# Sens_BMP085_HIH613x.net
KiCad netlist of a schematic drawn in EAGLE
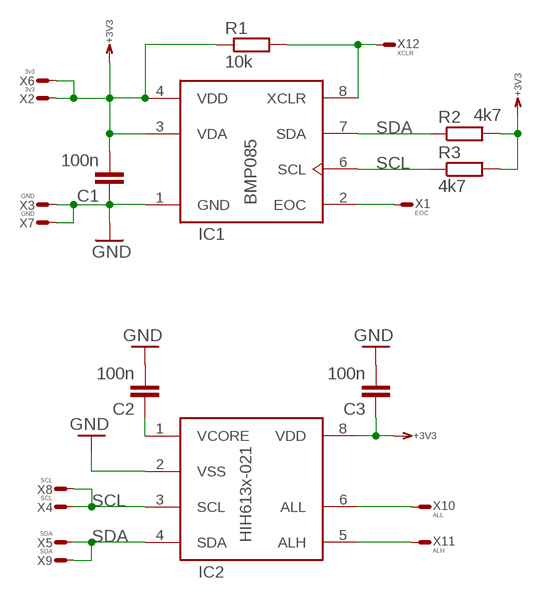
[diagram p0: schematic, sheet 1]

(export (version "E")
  (design (tool "Eeschema 10.0.6"))
  (components
    (comp (ref "C1")
      (value "100n")
      (footprint "eagle-import:0603")
      (libsource (lib "eagle-import") (part "C0603"))
    )
    (comp (ref "C2")
      (value "100n")
      (footprint "eagle-import:0603")
      (libsource (lib "eagle-import") (part "C0603"))
    )
    (comp (ref "C3")
      (value "100n")
      (footprint "eagle-import:0603")
      (libsource (lib "eagle-import") (part "C0603"))
    )
    (comp (ref "IC1")
      (value "BMP085")
      (footprint "eagle-import:LCC8")
      (libsource (lib "eagle-import") (part "BMP085"))
    )
    (comp (ref "IC2")
      (value "HIH613x-021")
      (footprint "eagle-import:SO8")
      (libsource (lib "eagle-import") (part "HIH613X"))
    )
    (comp (ref "R1")
      (value "10k")
      (footprint "eagle-import:0603")
      (libsource (lib "eagle-import") (part "R0603"))
    )
    (comp (ref "R2")
      (value "4k7")
      (footprint "eagle-import:0603")
      (libsource (lib "eagle-import") (part "R0603"))
    )
    (comp (ref "R3")
      (value "4k7")
      (footprint "eagle-import:0603")
      (libsource (lib "eagle-import") (part "R0603"))
    )
    (comp (ref "X1")
      (value "EOC")
      (footprint "eagle-import:S1.27R")
      (libsource (lib "eagle-import") (part "WIREPADR"))
    )
    (comp (ref "X2")
      (value "3v3")
      (footprint "eagle-import:T1.6_0.9")
      (libsource (lib "eagle-import") (part "WIREPADT1.6/0.9"))
    )
    (comp (ref "X3")
      (value "GND")
      (footprint "eagle-import:T1.6_0.9")
      (libsource (lib "eagle-import") (part "WIREPADT1.6/0.9"))
    )
    (comp (ref "X4")
      (value "SCL")
      (footprint "eagle-import:T1.6_0.9")
      (libsource (lib "eagle-import") (part "WIREPADT1.6/0.9"))
    )
    (comp (ref "X5")
      (value "SDA")
      (footprint "eagle-import:T1.6_0.9")
      (libsource (lib "eagle-import") (part "WIREPADT1.6/0.9"))
    )
    (comp (ref "X6")
      (value "3v3")
      (footprint "eagle-import:T1.6_0.9")
      (libsource (lib "eagle-import") (part "WIREPADT1.6/0.9"))
    )
    (comp (ref "X7")
      (value "GND")
      (footprint "eagle-import:T1.6_0.9")
      (libsource (lib "eagle-import") (part "WIREPADT1.6/0.9"))
    )
    (comp (ref "X8")
      (value "SCL")
      (footprint "eagle-import:T1.6_0.9")
      (libsource (lib "eagle-import") (part "WIREPADT1.6/0.9"))
    )
    (comp (ref "X9")
      (value "SDA")
      (footprint "eagle-import:T1.6_0.9")
      (libsource (lib "eagle-import") (part "WIREPADT1.6/0.9"))
    )
    (comp (ref "X10")
      (value "ALL")
      (footprint "eagle-import:S1.27R")
      (libsource (lib "eagle-import") (part "WIREPADR"))
    )
    (comp (ref "X11")
      (value "ALH")
      (footprint "eagle-import:S1.27R")
      (libsource (lib "eagle-import") (part "WIREPADR"))
    )
    (comp (ref "X12")
      (value "XCLR")
      (footprint "eagle-import:S1.27R")
      (libsource (lib "eagle-import") (part "WIREPADR"))
    )
  )
  (nets
    (net (code "1") (name "+3V3") (class "Default")
      (node (ref "C1") (pin "2") (pinfunction "2_2") (pintype "passive"))
      (node (ref "C3") (pin "1") (pinfunction "1_1") (pintype "passive"))
      (node (ref "IC1") (pin "3") (pinfunction "VDA_3") (pintype "input"))
      (node (ref "IC1") (pin "4") (pinfunction "VDD_4") (pintype "input"))
      (node (ref "IC2") (pin "8") (pinfunction "VDD_8") (pintype "bidirectional"))
      (node (ref "R1") (pin "1") (pinfunction "1_1") (pintype "passive"))
      (node (ref "R2") (pin "2") (pinfunction "2_2") (pintype "passive"))
      (node (ref "R3") (pin "2") (pinfunction "2_2") (pintype "passive"))
      (node (ref "X2") (pin "1") (pinfunction "S_1") (pintype "passive"))
      (node (ref "X6") (pin "1") (pinfunction "S_1") (pintype "passive"))
    )
    (net (code "2") (name "/SCL") (class "Default")
      (node (ref "IC1") (pin "6") (pinfunction "SCL_6") (pintype "input"))
      (node (ref "IC2") (pin "3") (pinfunction "SCL_3") (pintype "bidirectional"))
      (node (ref "R3") (pin "1") (pinfunction "1_1") (pintype "passive"))
      (node (ref "X4") (pin "1") (pinfunction "S_1") (pintype "passive"))
      (node (ref "X8") (pin "1") (pinfunction "S_1") (pintype "passive"))
    )
    (net (code "3") (name "/SDA") (class "Default")
      (node (ref "IC1") (pin "7") (pinfunction "SDA_7") (pintype "bidirectional"))
      (node (ref "IC2") (pin "4") (pinfunction "SDA_4") (pintype "bidirectional"))
      (node (ref "R2") (pin "1") (pinfunction "1_1") (pintype "passive"))
      (node (ref "X5") (pin "1") (pinfunction "S_1") (pintype "passive"))
      (node (ref "X9") (pin "1") (pinfunction "S_1") (pintype "passive"))
    )
    (net (code "4") (name "GND") (class "Default")
      (node (ref "C1") (pin "1") (pinfunction "1_1") (pintype "passive"))
      (node (ref "C2") (pin "2") (pinfunction "2_2") (pintype "passive"))
      (node (ref "C3") (pin "2") (pinfunction "2_2") (pintype "passive"))
      (node (ref "IC1") (pin "1") (pinfunction "GND_1") (pintype "input"))
      (node (ref "IC2") (pin "2") (pinfunction "VSS_2") (pintype "bidirectional"))
      (node (ref "X3") (pin "1") (pinfunction "S_1") (pintype "passive"))
      (node (ref "X7") (pin "1") (pinfunction "S_1") (pintype "passive"))
    )
    (net (code "5") (name "Net-(IC1-EOC)") (class "Default")
      (node (ref "IC1") (pin "2") (pinfunction "EOC_2") (pintype "output"))
      (node (ref "X1") (pin "1") (pinfunction "S_1") (pintype "passive"))
    )
    (net (code "6") (name "Net-(IC1-XCLR)") (class "Default")
      (node (ref "IC1") (pin "8") (pinfunction "XCLR_8") (pintype "input"))
      (node (ref "R1") (pin "2") (pinfunction "2_2") (pintype "passive"))
      (node (ref "X12") (pin "1") (pinfunction "S_1") (pintype "passive"))
    )
    (net (code "7") (name "Net-(IC2-ALH)") (class "Default")
      (node (ref "IC2") (pin "5") (pinfunction "ALH_5") (pintype "bidirectional"))
      (node (ref "X11") (pin "1") (pinfunction "S_1") (pintype "passive"))
    )
    (net (code "8") (name "Net-(IC2-ALL)") (class "Default")
      (node (ref "IC2") (pin "6") (pinfunction "ALL_6") (pintype "bidirectional"))
      (node (ref "X10") (pin "1") (pinfunction "S_1") (pintype "passive"))
    )
    (net (code "9") (name "Net-(IC2-VCORE)") (class "Default")
      (node (ref "C2") (pin "1") (pinfunction "1_1") (pintype "passive"))
      (node (ref "IC2") (pin "1") (pinfunction "VCORE_1") (pintype "bidirectional"))
    )
  )
)
